# 2layer_COB.net
KiCad netlist of a schematic drawn in Altium Designer
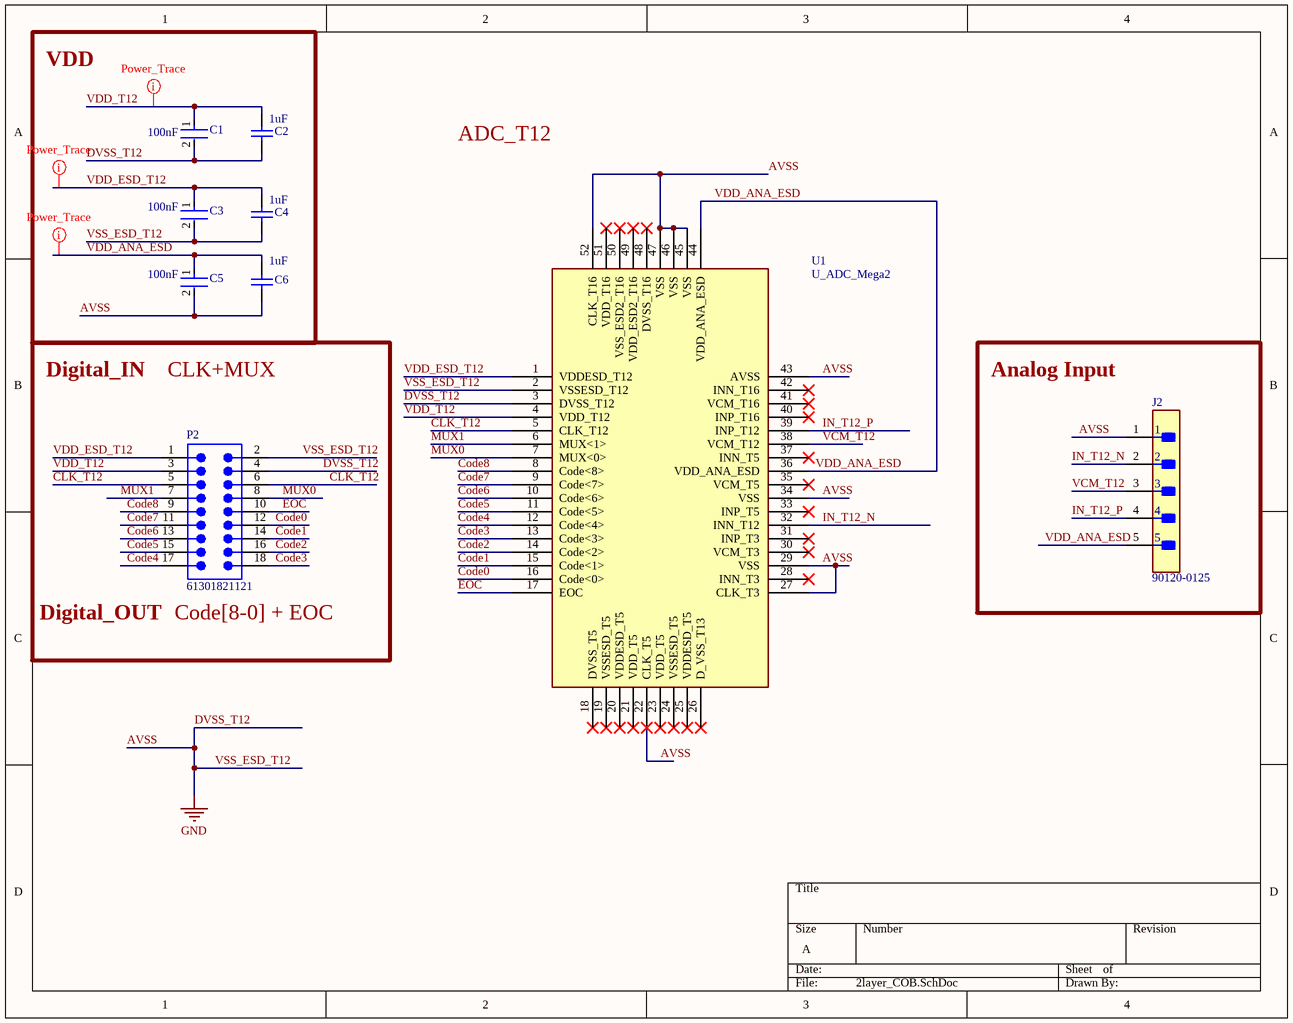
[diagram p0: 2layer_COB.SchDoc]

(export (version "E")
  (design (tool "Eeschema 10.0.6"))
  (components
    (comp (ref "C1")
      (value "08055C104KAT4A")
      (footprint "FP-0805-L_2_01_0_2-W_1_25-IPC_C")
      (description "CAP CER 0.1UF 50V X7R 0805")
      (fields
        (field (name "VOLTAGE") "50V")
        (field (name "CAPACITANCE") "100nF")
        (field (name "TOLERANCE") "10%")
      )
      (libsource (lib "Altium Content Vault") (part "11868f565c42a9108669ba33697ecf6"))
    )
    (comp (ref "C2")
      (value "1uF")
      (footprint "CAPC2013X140X50NL20T25")
      (fields
        (field (name "PART NUMBER") "08055D105KAT2A")
        (field (name "MANUFACTURER") "AVX Interconnect / Elco")
      )
      (libsource (lib "Altium Content Vault") (part "CAP"))
    )
    (comp (ref "C3")
      (value "08055C104KAT4A")
      (footprint "FP-0805-L_2_01_0_2-W_1_25-IPC_C")
      (description "CAP CER 0.1UF 50V X7R 0805")
      (fields
        (field (name "VOLTAGE") "50V")
        (field (name "CAPACITANCE") "100nF")
        (field (name "TOLERANCE") "10%")
      )
      (libsource (lib "Altium Content Vault") (part "11868f565c42a9108669ba33697ecf6"))
    )
    (comp (ref "C4")
      (value "1uF")
      (footprint "CAPC2013X140X50NL20T25")
      (fields
        (field (name "PART NUMBER") "08055D105KAT2A")
        (field (name "MANUFACTURER") "AVX Interconnect / Elco")
      )
      (libsource (lib "Altium Content Vault") (part "CAP"))
    )
    (comp (ref "C5")
      (value "08055C104KAT4A")
      (footprint "FP-0805-L_2_01_0_2-W_1_25-IPC_C")
      (description "CAP CER 0.1UF 50V X7R 0805")
      (fields
        (field (name "VOLTAGE") "50V")
        (field (name "CAPACITANCE") "100nF")
        (field (name "TOLERANCE") "10%")
      )
      (libsource (lib "Altium Content Vault") (part "11868f565c42a9108669ba33697ecf6"))
    )
    (comp (ref "C6")
      (value "1uF")
      (footprint "CAPC2013X140X50NL20T25")
      (fields
        (field (name "PART NUMBER") "08055D105KAT2A")
        (field (name "MANUFACTURER") "AVX Interconnect / Elco")
      )
      (libsource (lib "Altium Content Vault") (part "CAP"))
    )
    (comp (ref "J2")
      (value "90120-0125")
      (footprint "FP-90120-0125-MFG")
      (description "90120-0125 2.54mm Pitch C-Grid III Header, Single Row, Vertical, 5 Circuits, Tin (Sn) Plating")
      (libsource (lib "Altium Content Vault") (part "bf93c07fd2649a848d0ec8585582aab"))
    )
    (comp (ref "P2")
      (value "61301821121")
      (footprint "61301821121")
      (libsource (lib "Altium Content Vault") (part "Header_Male_2R_18P"))
    )
    (comp (ref "U1")
      (value "U_ADC_Mega2")
      (footprint "ADC_Team12")
      (description "MegaGroup2")
      (libsource (lib "ADC_T12") (part "U_ADC_Mega2"))
    )
  )
  (nets
    (net (code "1") (name "/CLK_T12") (class "Default")
      (node (ref "P2") (pin "5") (pinfunction "5_5") (pintype "passive"))
      (node (ref "P2") (pin "6") (pinfunction "6_6") (pintype "passive"))
      (node (ref "U1") (pin "5") (pinfunction "CLK_T12_5") (pintype "passive"))
    )
    (net (code "2") (name "/Code0") (class "Default")
      (node (ref "P2") (pin "12") (pinfunction "12_12") (pintype "passive"))
      (node (ref "U1") (pin "16") (pinfunction "Code<0>_16") (pintype "passive"))
    )
    (net (code "3") (name "/Code1") (class "Default")
      (node (ref "P2") (pin "14") (pinfunction "14_14") (pintype "passive"))
      (node (ref "U1") (pin "15") (pinfunction "Code<1>_15") (pintype "passive"))
    )
    (net (code "4") (name "/Code2") (class "Default")
      (node (ref "P2") (pin "16") (pinfunction "16_16") (pintype "passive"))
      (node (ref "U1") (pin "14") (pinfunction "Code<2>_14") (pintype "passive"))
    )
    (net (code "5") (name "/Code3") (class "Default")
      (node (ref "P2") (pin "18") (pinfunction "18_18") (pintype "passive"))
      (node (ref "U1") (pin "13") (pinfunction "Code<3>_13") (pintype "passive"))
    )
    (net (code "6") (name "/Code4") (class "Default")
      (node (ref "P2") (pin "17") (pinfunction "17_17") (pintype "passive"))
      (node (ref "U1") (pin "12") (pinfunction "Code<4>_12") (pintype "passive"))
    )
    (net (code "7") (name "/Code5") (class "Default")
      (node (ref "P2") (pin "15") (pinfunction "15_15") (pintype "passive"))
      (node (ref "U1") (pin "11") (pinfunction "Code<5>_11") (pintype "passive"))
    )
    (net (code "8") (name "/Code6") (class "Default")
      (node (ref "P2") (pin "13") (pinfunction "13_13") (pintype "passive"))
      (node (ref "U1") (pin "10") (pinfunction "Code<6>_10") (pintype "passive"))
    )
    (net (code "9") (name "/Code7") (class "Default")
      (node (ref "P2") (pin "11") (pinfunction "11_11") (pintype "passive"))
      (node (ref "U1") (pin "9") (pinfunction "Code<7>_9") (pintype "passive"))
    )
    (net (code "10") (name "/Code8") (class "Default")
      (node (ref "P2") (pin "9") (pinfunction "9_9") (pintype "passive"))
      (node (ref "U1") (pin "8") (pinfunction "Code<8>_8") (pintype "passive"))
    )
    (net (code "11") (name "/EOC") (class "Default")
      (node (ref "P2") (pin "10") (pinfunction "10_10") (pintype "passive"))
      (node (ref "U1") (pin "17") (pinfunction "EOC_17") (pintype "passive"))
    )
    (net (code "12") (name "/IN_T12_N") (class "Default")
      (node (ref "J2") (pin "2") (pinfunction "2_2") (pintype "passive"))
      (node (ref "U1") (pin "32") (pinfunction "INN_T12_32") (pintype "passive"))
    )
    (net (code "13") (name "/IN_T12_P") (class "Default")
      (node (ref "J2") (pin "4") (pinfunction "4_4") (pintype "passive"))
      (node (ref "U1") (pin "39") (pinfunction "INP_T12_39") (pintype "passive"))
    )
    (net (code "14") (name "/MUX0") (class "Default")
      (node (ref "P2") (pin "8") (pinfunction "8_8") (pintype "passive"))
      (node (ref "U1") (pin "7") (pinfunction "MUX<0>_7") (pintype "passive"))
    )
    (net (code "15") (name "/MUX1") (class "Default")
      (node (ref "P2") (pin "7") (pinfunction "7_7") (pintype "passive"))
      (node (ref "U1") (pin "6") (pinfunction "MUX<1>_6") (pintype "passive"))
    )
    (net (code "16") (name "/VCM_T12") (class "Default")
      (node (ref "J2") (pin "3") (pinfunction "3_3") (pintype "passive"))
      (node (ref "U1") (pin "38") (pinfunction "VCM_T12_38") (pintype "passive"))
    )
    (net (code "17") (name "/VDD_ANA_ESD") (class "Default")
      (node (ref "C5") (pin "1") (pinfunction "1_1") (pintype "passive"))
      (node (ref "C6") (pin "2") (pinfunction "2_2") (pintype "passive"))
      (node (ref "J2") (pin "5") (pinfunction "5_5") (pintype "passive"))
      (node (ref "U1") (pin "36") (pinfunction "VDD_ANA_ESD_36") (pintype "passive"))
      (node (ref "U1") (pin "44") (pinfunction "VDD_ANA_ESD_44") (pintype "passive"))
    )
    (net (code "18") (name "/VDD_ESD_T12") (class "Default")
      (node (ref "C3") (pin "1") (pinfunction "1_1") (pintype "passive"))
      (node (ref "C4") (pin "2") (pinfunction "2_2") (pintype "passive"))
      (node (ref "P2") (pin "1") (pinfunction "1_1") (pintype "passive"))
      (node (ref "U1") (pin "1") (pinfunction "VDDESD_T12_1") (pintype "passive"))
    )
    (net (code "19") (name "/VDD_T12") (class "Default")
      (node (ref "C1") (pin "1") (pinfunction "1_1") (pintype "passive"))
      (node (ref "C2") (pin "2") (pinfunction "2_2") (pintype "passive"))
      (node (ref "P2") (pin "3") (pinfunction "3_3") (pintype "passive"))
      (node (ref "U1") (pin "4") (pinfunction "VDD_T12_4") (pintype "passive"))
    )
    (net (code "20") (name "GND") (class "Default")
      (node (ref "C1") (pin "2") (pinfunction "2_2") (pintype "passive"))
      (node (ref "C2") (pin "1") (pinfunction "1_1") (pintype "passive"))
      (node (ref "C3") (pin "2") (pinfunction "2_2") (pintype "passive"))
      (node (ref "C4") (pin "1") (pinfunction "1_1") (pintype "passive"))
      (node (ref "C5") (pin "2") (pinfunction "2_2") (pintype "passive"))
      (node (ref "C6") (pin "1") (pinfunction "1_1") (pintype "passive"))
      (node (ref "J2") (pin "1") (pinfunction "1_1") (pintype "passive"))
      (node (ref "P2") (pin "2") (pinfunction "2_2") (pintype "passive"))
      (node (ref "P2") (pin "4") (pinfunction "4_4") (pintype "passive"))
      (node (ref "U1") (pin "2") (pinfunction "VSSESD_T12_2") (pintype "passive"))
      (node (ref "U1") (pin "22") (pinfunction "CLK_T5_22") (pintype "passive"))
      (node (ref "U1") (pin "27") (pinfunction "CLK_T3_27") (pintype "passive"))
      (node (ref "U1") (pin "29") (pinfunction "VSS_29") (pintype "passive"))
      (node (ref "U1") (pin "3") (pinfunction "DVSS_T12_3") (pintype "passive"))
      (node (ref "U1") (pin "34") (pinfunction "VSS_34") (pintype "passive"))
      (node (ref "U1") (pin "43") (pinfunction "AVSS_43") (pintype "passive"))
      (node (ref "U1") (pin "45") (pinfunction "VSS_45") (pintype "passive"))
      (node (ref "U1") (pin "46") (pinfunction "VSS_46") (pintype "passive"))
      (node (ref "U1") (pin "47") (pinfunction "VSS_47") (pintype "passive"))
      (node (ref "U1") (pin "52") (pinfunction "CLK_T16_52") (pintype "passive"))
    )
    (net (code "21") (name "unconnected-(U1-DVSS_T5-Pad18)") (class "Default")
      (node (ref "U1") (pin "18") (pinfunction "DVSS_T5_18") (pintype "passive+no_connect"))
    )
    (net (code "22") (name "unconnected-(U1-DVSS_T16-Pad48)") (class "Default")
      (node (ref "U1") (pin "48") (pinfunction "DVSS_T16_48") (pintype "passive+no_connect"))
    )
    (net (code "23") (name "unconnected-(U1-D_VSS_T13-Pad26)") (class "Default")
      (node (ref "U1") (pin "26") (pinfunction "D_VSS_T13_26") (pintype "passive+no_connect"))
    )
    (net (code "24") (name "unconnected-(U1-INN_T3-Pad28)") (class "Default")
      (node (ref "U1") (pin "28") (pinfunction "INN_T3_28") (pintype "passive+no_connect"))
    )
    (net (code "25") (name "unconnected-(U1-INN_T5-Pad37)") (class "Default")
      (node (ref "U1") (pin "37") (pinfunction "INN_T5_37") (pintype "passive+no_connect"))
    )
    (net (code "26") (name "unconnected-(U1-INN_T16-Pad42)") (class "Default")
      (node (ref "U1") (pin "42") (pinfunction "INN_T16_42") (pintype "passive+no_connect"))
    )
    (net (code "27") (name "unconnected-(U1-INP_T3-Pad31)") (class "Default")
      (node (ref "U1") (pin "31") (pinfunction "INP_T3_31") (pintype "passive+no_connect"))
    )
    (net (code "28") (name "unconnected-(U1-INP_T5-Pad33)") (class "Default")
      (node (ref "U1") (pin "33") (pinfunction "INP_T5_33") (pintype "passive+no_connect"))
    )
    (net (code "29") (name "unconnected-(U1-INP_T16-Pad40)") (class "Default")
      (node (ref "U1") (pin "40") (pinfunction "INP_T16_40") (pintype "passive+no_connect"))
    )
    (net (code "30") (name "unconnected-(U1-VCM_T3-Pad30)") (class "Default")
      (node (ref "U1") (pin "30") (pinfunction "VCM_T3_30") (pintype "passive+no_connect"))
    )
    (net (code "31") (name "unconnected-(U1-VCM_T5-Pad35)") (class "Default")
      (node (ref "U1") (pin "35") (pinfunction "VCM_T5_35") (pintype "passive+no_connect"))
    )
    (net (code "32") (name "unconnected-(U1-VCM_T16-Pad41)") (class "Default")
      (node (ref "U1") (pin "41") (pinfunction "VCM_T16_41") (pintype "passive+no_connect"))
    )
    (net (code "33") (name "unconnected-(U1-VDDESD_T5-Pad20)") (class "Default")
      (node (ref "U1") (pin "20") (pinfunction "VDDESD_T5_20") (pintype "passive+no_connect"))
    )
    (net (code "34") (name "unconnected-(U1-VDDESD_T5-Pad25)") (class "Default")
      (node (ref "U1") (pin "25") (pinfunction "VDDESD_T5_25") (pintype "passive+no_connect"))
    )
    (net (code "35") (name "unconnected-(U1-VDD_ESD2_T16-Pad49)") (class "Default")
      (node (ref "U1") (pin "49") (pinfunction "VDD_ESD2_T16_49") (pintype "passive+no_connect"))
    )
    (net (code "36") (name "unconnected-(U1-VDD_T5-Pad21)") (class "Default")
      (node (ref "U1") (pin "21") (pinfunction "VDD_T5_21") (pintype "passive+no_connect"))
    )
    (net (code "37") (name "unconnected-(U1-VDD_T5-Pad23)") (class "Default")
      (node (ref "U1") (pin "23") (pinfunction "VDD_T5_23") (pintype "passive+no_connect"))
    )
    (net (code "38") (name "unconnected-(U1-VDD_T16-Pad51)") (class "Default")
      (node (ref "U1") (pin "51") (pinfunction "VDD_T16_51") (pintype "passive+no_connect"))
    )
    (net (code "39") (name "unconnected-(U1-VSSESD_T5-Pad19)") (class "Default")
      (node (ref "U1") (pin "19") (pinfunction "VSSESD_T5_19") (pintype "passive+no_connect"))
    )
    (net (code "40") (name "unconnected-(U1-VSSESD_T5-Pad24)") (class "Default")
      (node (ref "U1") (pin "24") (pinfunction "VSSESD_T5_24") (pintype "passive+no_connect"))
    )
    (net (code "41") (name "unconnected-(U1-VSS_ESD2_T16-Pad50)") (class "Default")
      (node (ref "U1") (pin "50") (pinfunction "VSS_ESD2_T16_50") (pintype "passive+no_connect"))
    )
  )
)
